# STM_System_Board_Supply.net
KiCad netlist of a schematic drawn in Altium Designer
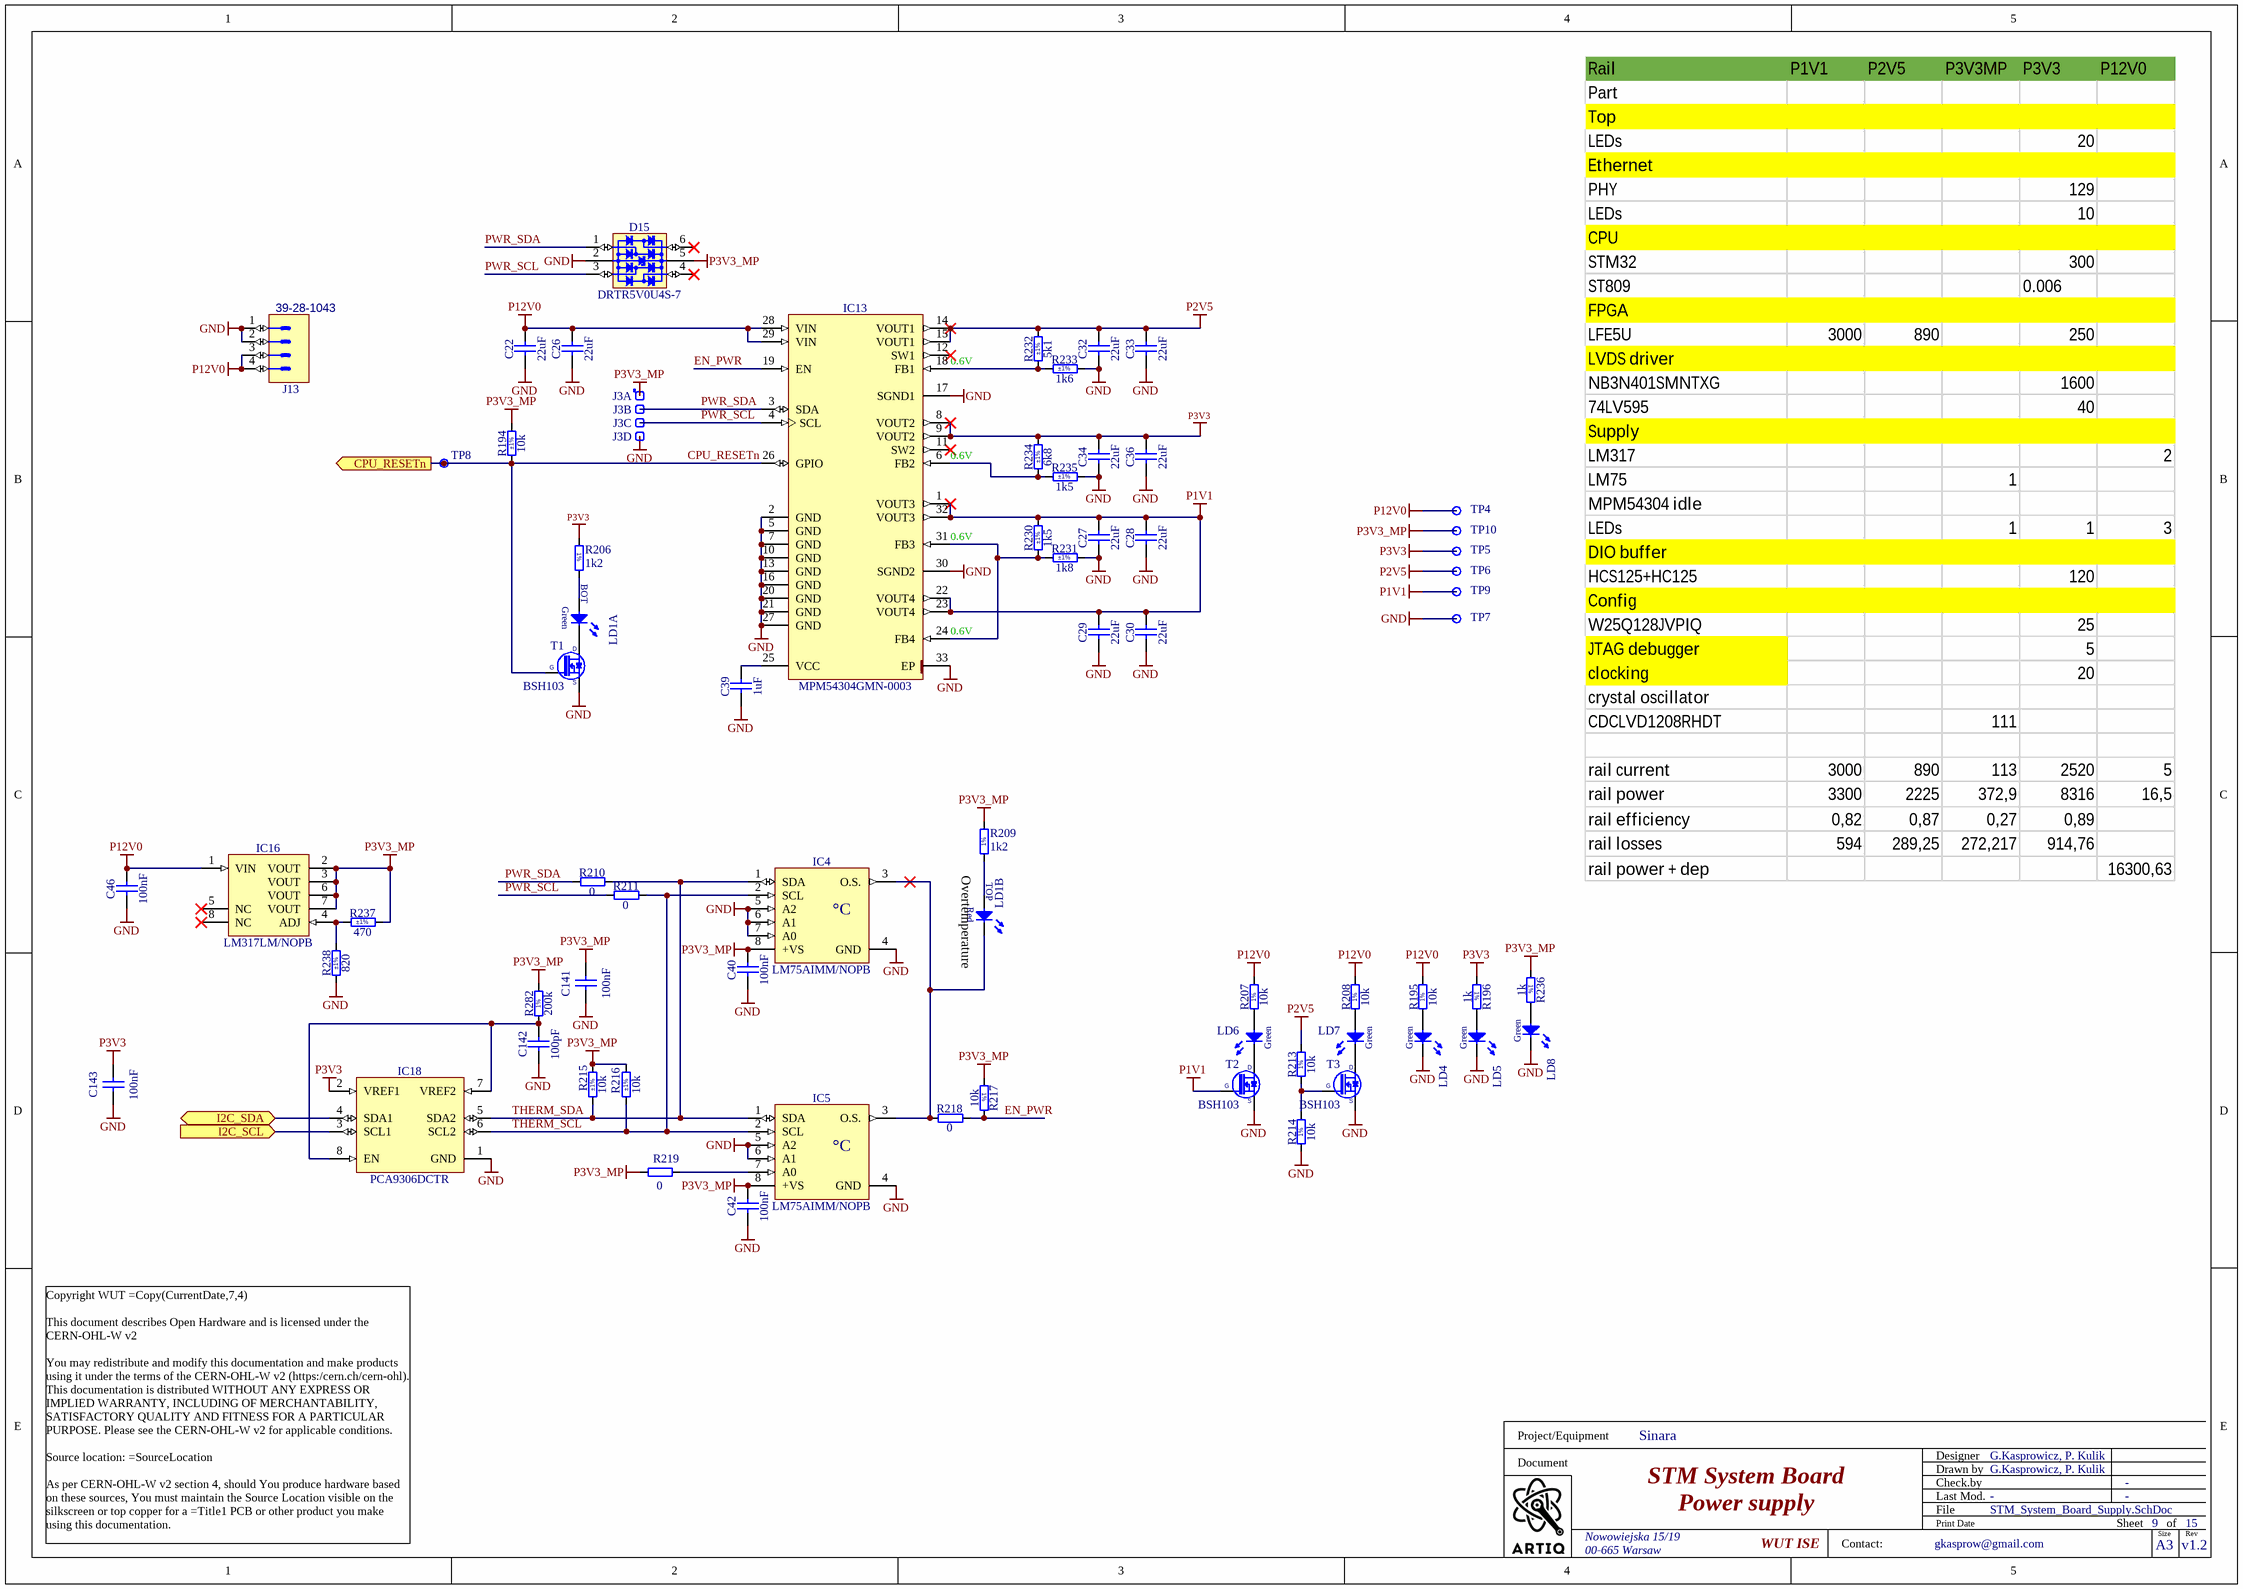
[diagram p0: STM_System_Board_Supply.SchDoc]

(export (version "E")
  (design (tool "Eeschema 10.0.6"))
  (components
    (comp (ref "C22")
      (value "22uF")
      (footprint "CAPC2012X135N")
      (description "Non-polarised capacitor")
      (fields
        (field (name "PART NUMBER") "CC0805_22UF_16V_10%_X5R")
        (field (name "VOLTAGE") "16V")
        (field (name "AUTHOR") "CERN DEM JLC")
      )
      (libsource (lib "Capacitors") (part "Capacitor - non polarized"))
    )
    (comp (ref "C26")
      (value "22uF")
      (footprint "CAPC2012X135N")
      (description "Non-polarised capacitor")
      (fields
        (field (name "PART NUMBER") "CC0805_22UF_16V_10%_X5R")
        (field (name "VOLTAGE") "16V")
        (field (name "AUTHOR") "CERN DEM JLC")
      )
      (libsource (lib "Capacitors") (part "Capacitor - non polarized"))
    )
    (comp (ref "C27")
      (value "22uF")
      (footprint "CAPC2012X135N")
      (description "Non-polarised capacitor")
      (fields
        (field (name "PART NUMBER") "CC0805_22UF_16V_10%_X5R")
        (field (name "VOLTAGE") "16V")
        (field (name "AUTHOR") "CERN DEM JLC")
      )
      (libsource (lib "Capacitors") (part "Capacitor - non polarized"))
    )
    (comp (ref "C28")
      (value "22uF")
      (footprint "CAPC2012X135N")
      (description "Non-polarised capacitor")
      (fields
        (field (name "PART NUMBER") "CC0805_22UF_16V_10%_X5R")
        (field (name "VOLTAGE") "16V")
        (field (name "AUTHOR") "CERN DEM JLC")
      )
      (libsource (lib "Capacitors") (part "Capacitor - non polarized"))
    )
    (comp (ref "C29")
      (value "22uF")
      (footprint "CAPC2012X135N")
      (description "Non-polarised capacitor")
      (fields
        (field (name "PART NUMBER") "CC0805_22UF_16V_10%_X5R")
        (field (name "VOLTAGE") "16V")
        (field (name "AUTHOR") "CERN DEM JLC")
      )
      (libsource (lib "Capacitors") (part "Capacitor - non polarized"))
    )
    (comp (ref "C30")
      (value "22uF")
      (footprint "CAPC2012X135N")
      (description "Non-polarised capacitor")
      (fields
        (field (name "PART NUMBER") "CC0805_22UF_16V_10%_X5R")
        (field (name "VOLTAGE") "16V")
        (field (name "AUTHOR") "CERN DEM JLC")
      )
      (libsource (lib "Capacitors") (part "Capacitor - non polarized"))
    )
    (comp (ref "C32")
      (value "22uF")
      (footprint "CAPC2012X135N")
      (description "Non-polarised capacitor")
      (fields
        (field (name "PART NUMBER") "CC0805_22UF_16V_10%_X5R")
        (field (name "VOLTAGE") "16V")
        (field (name "AUTHOR") "CERN DEM JLC")
      )
      (libsource (lib "Capacitors") (part "Capacitor - non polarized"))
    )
    (comp (ref "C33")
      (value "22uF")
      (footprint "CAPC2012X135N")
      (description "Non-polarised capacitor")
      (fields
        (field (name "PART NUMBER") "CC0805_22UF_16V_10%_X5R")
        (field (name "VOLTAGE") "16V")
        (field (name "AUTHOR") "CERN DEM JLC")
      )
      (libsource (lib "Capacitors") (part "Capacitor - non polarized"))
    )
    (comp (ref "C34")
      (value "22uF")
      (footprint "CAPC2012X135N")
      (description "Non-polarised capacitor")
      (fields
        (field (name "PART NUMBER") "CC0805_22UF_16V_10%_X5R")
        (field (name "VOLTAGE") "16V")
        (field (name "AUTHOR") "CERN DEM JLC")
      )
      (libsource (lib "Capacitors") (part "Capacitor - non polarized"))
    )
    (comp (ref "C36")
      (value "22uF")
      (footprint "CAPC2012X135N")
      (description "Non-polarised capacitor")
      (fields
        (field (name "PART NUMBER") "CC0805_22UF_16V_10%_X5R")
        (field (name "VOLTAGE") "16V")
        (field (name "AUTHOR") "CERN DEM JLC")
      )
      (libsource (lib "Capacitors") (part "Capacitor - non polarized"))
    )
    (comp (ref "C39")
      (value "1uF")
      (footprint "CAPC1005X55N")
      (description "Non-polarised capacitor")
      (fields
        (field (name "PART NUMBER") "CC0402_1UF_16V_10%_X5R")
        (field (name "VOLTAGE") "16V")
        (field (name "AUTHOR") "CERN DEM JLC")
      )
      (libsource (lib "Capacitors") (part "Capacitor - non polarized"))
    )
    (comp (ref "C40")
      (value "100nF")
      (footprint "CAPC1005X55N")
      (description "Non-polarised capacitor")
      (fields
        (field (name "PART NUMBER") "CC0402_100NF_16V_10%_X5R")
        (field (name "VOLTAGE") "16V")
        (field (name "AUTHOR") "CERN DEM JLC")
      )
      (libsource (lib "Capacitors") (part "Capacitor - non polarized"))
    )
    (comp (ref "C42")
      (value "100nF")
      (footprint "CAPC1005X55N")
      (description "Non-polarised capacitor")
      (fields
        (field (name "PART NUMBER") "CC0402_100NF_16V_10%_X5R")
        (field (name "VOLTAGE") "16V")
        (field (name "AUTHOR") "CERN DEM JLC")
      )
      (libsource (lib "Capacitors") (part "Capacitor - non polarized"))
    )
    (comp (ref "C46")
      (value "100nF")
      (footprint "CAPC1005X55N")
      (description "Non-polarised capacitor")
      (fields
        (field (name "PART NUMBER") "CC0402_100NF_16V_10%_X5R")
        (field (name "VOLTAGE") "16V")
        (field (name "AUTHOR") "CERN DEM JLC")
      )
      (libsource (lib "Capacitors") (part "Capacitor - non polarized"))
    )
    (comp (ref "C141")
      (value "100nF")
      (footprint "CAPC1005X55N")
      (description "Non-polarised capacitor")
      (fields
        (field (name "PART NUMBER") "CC0402_100NF_16V_10%_X5R")
        (field (name "VOLTAGE") "16V")
        (field (name "AUTHOR") "CERN DEM JLC")
      )
      (libsource (lib "Capacitors") (part "Capacitor - non polarized"))
    )
    (comp (ref "C142")
      (value "100pF")
      (footprint "CAPC1005X55N")
      (description "Non-polarised capacitor")
      (fields
        (field (name "PART NUMBER") "CC0402_100PF_50V_5%_C0G")
        (field (name "VOLTAGE") "50V")
        (field (name "AUTHOR") "CERN DEM JLC")
      )
      (libsource (lib "Capacitors") (part "Capacitor - non polarized"))
    )
    (comp (ref "C143")
      (value "100nF")
      (footprint "CAPC1005X55N")
      (description "Non-polarised capacitor")
      (fields
        (field (name "PART NUMBER") "CC0402_100NF_16V_10%_X5R")
        (field (name "VOLTAGE") "16V")
        (field (name "AUTHOR") "CERN DEM JLC")
      )
      (libsource (lib "Capacitors") (part "Capacitor - non polarized"))
    )
    (comp (ref "D15")
      (value "DRTR5V0U4S-7")
      (footprint "SOT65P210X110-6N")
      (description "Integrated Quad Ultra-Low Capacitance ESD Protection")
      (fields (field (name "MANUFACTURER") "DIODES") (field (name "AUTHOR") "GK"))
      (libsource (lib "Diodes") (part "D_TVS_DRTR5V0U4S-7"))
    )
    (comp (ref "IC4")
      (value "LM75AIMM/NOPB")
      (footprint "SOP65P490X109-8N")
      (description "Digital Temperature Sensor and Thermal Watchdog with Two-Wire Interface")
      (fields (field (name "MANUFACTURER") "TEXAS INSTRUMENTS") (field (name "AUTHOR") "CERN DEM JLC"))
      (libsource (lib "ICs And Semiconductors") (part "LM75"))
    )
    (comp (ref "IC5")
      (value "LM75AIMM/NOPB")
      (footprint "SOP65P490X109-8N")
      (description "Digital Temperature Sensor and Thermal Watchdog with Two-Wire Interface")
      (fields (field (name "MANUFACTURER") "TEXAS INSTRUMENTS") (field (name "AUTHOR") "CERN DEM JLC"))
      (libsource (lib "ICs And Semiconductors") (part "LM75"))
    )
    (comp (ref "IC13")
      (value "MPM54304GMN-0003")
      (footprint "MPS_MPM54304GMN")
      (description "Quad-Output Power Module with I2C and MTP")
      (fields
        (field (name "MANUFACTURER") "MPS (MONOLITIC  POWER SYSTEMS)")
        (field (name "AUTHOR") "CERN DEM BC")
      )
      (libsource (lib "ICs And Semiconductors") (part "MPM54304GMN"))
    )
    (comp (ref "IC16")
      (value "LM317LM/NOPB")
      (footprint "SOIC127P600X175-8N")
      (description "1.2V to 37V, 100mA Adjustable Positive Regulator")
      (fields (field (name "MANUFACTURER") "TEXAS INSTRUMENTS") (field (name "AUTHOR") "CERN DEM JLC"))
      (libsource (lib "ICs And Semiconductors") (part "LM317LM"))
    )
    (comp (ref "IC18")
      (value "PCA9306DCTR")
      (footprint "SOP65P400X130-8N")
      (description "Dual Bidirectional I2C Bus And SMBus Voltage-Level Translator")
      (fields (field (name "MANUFACTURER") "TEXAS INSTRUMENTS") (field (name "AUTHOR") "CERN DEM JLC"))
      (libsource (lib "ICs And Semiconductors") (part "PCA9306D"))
    )
    (comp (ref "J3")
      (value "Header 4")
      (footprint "SAMTEC_HTSW-104-23-L-S")
      (description "4 Mini Wire-Wrap Contact Strip Header")
      (fields
        (field (name "PART NUMBER") "SAMTEC_HTSW-104-23-L-S")
        (field (name "MANUFACTURER") "SAMTEC")
        (field (name "AUTHOR") "CERN DEM JLC")
      )
      (libsource (lib "Connectors") (part "Wire-Wrap Contact x4"))
    )
    (comp (ref "J13")
      (value "Mini-Fit Jr.™")
      (footprint "MOLEX_39-28-1043")
      (description "Connector 4 Male")
      (fields
        (field (name "MANUFACTURER PART NUMBER") "39-28-1043")
        (field (name "MANUFACTURER") "MOLEX")
        (field (name "PART NUMBER") "MOLEX_39-28-1043")
        (field (name "AUTHOR") "CERN DEM JLC")
      )
      (libsource (lib "Connectors") (part "Connector 4 Male"))
    )
    (comp (ref "LD1")
      (value "Red/Green")
      (footprint "LED_DIALIGHT_571-0112F")
      (description "2x LED  Botom Green, Top Red")
      (fields
        (field (name "PART NUMBER") "LED_DIALIGHT_571-0112F")
        (field (name "MANUFACTURER") "DIALIGHT")
        (field (name "AUTHOR") "CERN DEM JLC")
      )
      (libsource (lib "ICs And Semiconductors") (part "LED x2 G-1C2A-BOT_R-3C4A-TOP"))
    )
    (comp (ref "LD4")
      (value "Green")
      (footprint "LED_KINGBRIGHT_KPH-1608CGCK")
      (description "LED Green 1C 2A")
      (fields
        (field (name "PART NUMBER") "LED_KINGBRIGHT_KPH-1608CGCK")
        (field (name "MANUFACTURER") "KINGBRIGHT")
        (field (name "AUTHOR") "CERN DEM JLC")
      )
      (libsource (lib "ICs And Semiconductors") (part "LED Green 1C 2A"))
    )
    (comp (ref "LD5")
      (value "Green")
      (footprint "LED_KINGBRIGHT_KPH-1608CGCK")
      (description "LED Green 1C 2A")
      (fields
        (field (name "PART NUMBER") "LED_KINGBRIGHT_KPH-1608CGCK")
        (field (name "MANUFACTURER") "KINGBRIGHT")
        (field (name "AUTHOR") "CERN DEM JLC")
      )
      (libsource (lib "ICs And Semiconductors") (part "LED Green 1C 2A"))
    )
    (comp (ref "LD6")
      (value "Green")
      (footprint "LED_KINGBRIGHT_KPH-1608CGCK")
      (description "LED Green 1C 2A")
      (fields
        (field (name "MANUFACTURER PART NUMBER") "KPH-1608CGCK")
        (field (name "PART NUMBER") "LED_KINGBRIGHT_KPH-1608CGCK")
        (field (name "AUTHOR") "CERN DEM JLC")
      )
      (libsource (lib "ICs And Semiconductors") (part "LED Green 1C 2A"))
    )
    (comp (ref "LD7")
      (value "Green")
      (footprint "LED_KINGBRIGHT_KPH-1608CGCK")
      (description "LED Green 1C 2A")
      (fields
        (field (name "MANUFACTURER PART NUMBER") "KPH-1608CGCK")
        (field (name "PART NUMBER") "LED_KINGBRIGHT_KPH-1608CGCK")
        (field (name "AUTHOR") "CERN DEM JLC")
      )
      (libsource (lib "ICs And Semiconductors") (part "LED Green 1C 2A"))
    )
    (comp (ref "LD8")
      (value "Green")
      (footprint "LED_KINGBRIGHT_KPH-1608CGCK")
      (description "LED Green 1C 2A")
      (fields
        (field (name "PART NUMBER") "LED_KINGBRIGHT_KPH-1608CGCK")
        (field (name "MANUFACTURER") "KINGBRIGHT")
        (field (name "AUTHOR") "CERN DEM JLC")
      )
      (libsource (lib "ICs And Semiconductors") (part "LED Green 1C 2A"))
    )
    (comp (ref "R194")
      (value "10k")
      (footprint "RESC1005X40N")
      (description "Resistor - 1%")
      (fields
        (field (name "TOLERANCE") "±1%")
        (field (name "PART NUMBER") "R0402_10K_1%_0.0625W_100PPM")
        (field (name "POWER") "0.0625W")
        (field (name "AUTHOR") "CERN DEM JLC")
      )
      (libsource (lib "Resistors") (part "Resistor - 1%"))
    )
    (comp (ref "R195")
      (value "10k")
      (footprint "RESC1005X40N")
      (description "Resistor - 1%")
      (fields
        (field (name "PART NUMBER") "R0402_10K_1%_0.0625W_100PPM")
        (field (name "POWER") "0.0625W")
        (field (name "AUTHOR") "CERN DEM JLC")
      )
      (libsource (lib "Resistors") (part "Resistor - 1%"))
    )
    (comp (ref "R196")
      (value "1k")
      (footprint "RESC1608X55N")
      (description "Resistor - 1%")
      (fields
        (field (name "PART NUMBER") "R0603_1K_1%_0.1W_100PPM")
        (field (name "POWER") "0.1W")
        (field (name "AUTHOR") "CERN DEM JLC")
      )
      (libsource (lib "Resistors") (part "Resistor - 1%"))
    )
    (comp (ref "R206")
      (value "1k2")
      (footprint "RESC1608X55N")
      (description "Resistor - 1%")
      (fields
        (field (name "PART NUMBER") "R0603_1K2_1%_0.1W_100PPM")
        (field (name "POWER") "0.1W")
        (field (name "AUTHOR") "CERN DEM JLC")
      )
      (libsource (lib "Resistors") (part "Resistor - 1%"))
    )
    (comp (ref "R207")
      (value "10k")
      (footprint "RESC1005X40N")
      (description "Resistor - 1%")
      (fields
        (field (name "PART NUMBER") "R0402_10K_1%_0.0625W_100PPM")
        (field (name "POWER") "0.0625W")
        (field (name "AUTHOR") "CERN DEM JLC")
      )
      (libsource (lib "Resistors") (part "Resistor - 1%"))
    )
    (comp (ref "R208")
      (value "10k")
      (footprint "RESC1005X40N")
      (description "Resistor - 1%")
      (fields
        (field (name "PART NUMBER") "R0402_10K_1%_0.0625W_100PPM")
        (field (name "POWER") "0.0625W")
        (field (name "AUTHOR") "CERN DEM JLC")
      )
      (libsource (lib "Resistors") (part "Resistor - 1%"))
    )
    (comp (ref "R209")
      (value "1k2")
      (footprint "RESC1608X55N")
      (description "Resistor - 1%")
      (fields
        (field (name "PART NUMBER") "R0603_1K2_1%_0.1W_100PPM")
        (field (name "POWER") "0.1W")
        (field (name "AUTHOR") "CERN DEM JLC")
      )
      (libsource (lib "Resistors") (part "Resistor - 1%"))
    )
    (comp (ref "R210")
      (value "0")
      (footprint "RESC1005X40N")
      (description "Resistor")
      (fields
        (field (name "PART NUMBER") "R0402_0R_JUMPER")
        (field (name "MANUFACTURER") "GENERIC")
        (field (name "AUTHOR") "CERN DEM JLC")
      )
      (libsource (lib "Resistors") (part "Resistor"))
    )
    (comp (ref "R211")
      (value "0")
      (footprint "RESC1005X40N")
      (description "Resistor")
      (fields
        (field (name "PART NUMBER") "R0402_0R_JUMPER")
        (field (name "MANUFACTURER") "GENERIC")
        (field (name "AUTHOR") "CERN DEM JLC")
      )
      (libsource (lib "Resistors") (part "Resistor"))
    )
    (comp (ref "R213")
      (value "10k")
      (footprint "RESC1005X40N")
      (description "Resistor - 1%")
      (fields
        (field (name "PART NUMBER") "R0402_10K_1%_0.0625W_100PPM")
        (field (name "POWER") "0.0625W")
        (field (name "AUTHOR") "CERN DEM JLC")
      )
      (libsource (lib "Resistors") (part "Resistor - 1%"))
    )
    (comp (ref "R214")
      (value "10k")
      (footprint "RESC1005X40N")
      (description "Resistor - 1%")
      (fields
        (field (name "PART NUMBER") "R0402_10K_1%_0.0625W_100PPM")
        (field (name "POWER") "0.0625W")
        (field (name "AUTHOR") "CERN DEM JLC")
      )
      (libsource (lib "Resistors") (part "Resistor - 1%"))
    )
    (comp (ref "R215")
      (value "10k")
      (footprint "RESC1005X40N")
      (description "Resistor - 1%")
      (fields
        (field (name "PART NUMBER") "R0402_10K_1%_0.0625W_100PPM")
        (field (name "POWER") "0.0625W")
        (field (name "TOLERANCE") "±1%")
        (field (name "AUTHOR") "CERN DEM JLC")
      )
      (libsource (lib "Resistors") (part "Resistor - 1%"))
    )
    (comp (ref "R216")
      (value "10k")
      (footprint "RESC1005X40N")
      (description "Resistor - 1%")
      (fields
        (field (name "PART NUMBER") "R0402_10K_1%_0.0625W_100PPM")
        (field (name "POWER") "0.0625W")
        (field (name "TOLERANCE") "±1%")
        (field (name "AUTHOR") "CERN DEM JLC")
      )
      (libsource (lib "Resistors") (part "Resistor - 1%"))
    )
    (comp (ref "R217")
      (value "10k")
      (footprint "RESC1005X40N")
      (description "Resistor - 1%")
      (fields
        (field (name "PART NUMBER") "R0402_10K_1%_0.0625W_100PPM")
        (field (name "POWER") "0.0625W")
        (field (name "AUTHOR") "CERN DEM JLC")
      )
      (libsource (lib "Resistors") (part "Resistor - 1%"))
    )
    (comp (ref "R218")
      (value "0")
      (footprint "RESC1005X40N")
      (description "Resistor")
      (fields
        (field (name "PART NUMBER") "R0402_0R_JUMPER")
        (field (name "MANUFACTURER") "GENERIC")
        (field (name "AUTHOR") "CERN DEM JLC")
      )
      (libsource (lib "Resistors") (part "Resistor"))
    )
    (comp (ref "R219")
      (value "0")
      (footprint "RESC1005X40N")
      (description "Resistor")
      (fields
        (field (name "PART NUMBER") "R0402_0R_JUMPER")
        (field (name "MANUFACTURER") "GENERIC")
        (field (name "AUTHOR") "CERN DEM JLC")
      )
      (libsource (lib "Resistors") (part "Resistor"))
    )
    (comp (ref "R230")
      (value "1k5")
      (footprint "RESC1005X40N")
      (description "Resistor - 1%")
      (fields
        (field (name "TOLERANCE") "±1%")
        (field (name "PART NUMBER") "R0402_1K5_1%_0.0625W_100PPM")
        (field (name "POWER") "0.0625W")
        (field (name "AUTHOR") "CERN DEM JLC")
      )
      (libsource (lib "Resistors") (part "Resistor - 1%"))
    )
    (comp (ref "R231")
      (value "1k8")
      (footprint "RESC1005X40N")
      (description "Resistor - 1%")
      (fields
        (field (name "TOLERANCE") "±1%")
        (field (name "PART NUMBER") "R0402_1K8_1%_0.0625W_100PPM")
        (field (name "POWER") "0.0625W")
        (field (name "AUTHOR") "CERN DEM JLC")
      )
      (libsource (lib "Resistors") (part "Resistor - 1%"))
    )
    (comp (ref "R232")
      (value "5k1")
      (footprint "RESC1005X40N")
      (description "Resistor - 1%")
      (fields
        (field (name "TOLERANCE") "±1%")
        (field (name "PART NUMBER") "R0402_5K1_1%_0.0625W_100PPM")
        (field (name "POWER") "0.0625W")
        (field (name "AUTHOR") "CERN DEM JLC")
      )
      (libsource (lib "Resistors") (part "Resistor - 1%"))
    )
    (comp (ref "R233")
      (value "1k6")
      (footprint "RESC1005X40N")
      (description "Resistor - 1%")
      (fields
        (field (name "TOLERANCE") "±1%")
        (field (name "PART NUMBER") "R0402_1K6_1%_0.0625W_100PPM")
        (field (name "POWER") "0.0625W")
        (field (name "AUTHOR") "CERN DEM JLC")
      )
      (libsource (lib "Resistors") (part "Resistor - 1%"))
    )
    (comp (ref "R234")
      (value "6k8")
      (footprint "RESC1005X40N")
      (description "Resistor - 1%")
      (fields
        (field (name "TOLERANCE") "±1%")
        (field (name "PART NUMBER") "R0402_6K8_1%_0.0625W_100PPM")
        (field (name "POWER") "0.0625W")
        (field (name "AUTHOR") "CERN DEM JLC")
      )
      (libsource (lib "Resistors") (part "Resistor - 1%"))
    )
    (comp (ref "R235")
      (value "1k5")
      (footprint "RESC1005X40N")
      (description "Resistor - 1%")
      (fields
        (field (name "TOLERANCE") "±1%")
        (field (name "PART NUMBER") "R0402_1K5_1%_0.0625W_100PPM")
        (field (name "POWER") "0.0625W")
        (field (name "AUTHOR") "CERN DEM JLC")
      )
      (libsource (lib "Resistors") (part "Resistor - 1%"))
    )
    (comp (ref "R236")
      (value "1k")
      (footprint "RESC1608X55N")
      (description "Resistor - 1%")
      (fields
        (field (name "PART NUMBER") "R0603_1K_1%_0.1W_100PPM")
        (field (name "POWER") "0.1W")
        (field (name "AUTHOR") "CERN DEM JLC")
      )
      (libsource (lib "Resistors") (part "Resistor - 1%"))
    )
    (comp (ref "R237")
      (value "470")
      (footprint "RESC1005X40N")
      (description "Resistor - 1%")
      (fields
        (field (name "TOLERANCE") "±1%")
        (field (name "PART NUMBER") "R0402_470R_1%_0.0625W_100PPM")
        (field (name "POWER") "0.0625W")
        (field (name "AUTHOR") "CERN DEM JLC")
      )
      (libsource (lib "Resistors") (part "Resistor - 1%"))
    )
    (comp (ref "R238")
      (value "820")
      (footprint "RESC1005X40N")
      (description "Resistor - 1%")
      (fields
        (field (name "TOLERANCE") "±1%")
        (field (name "PART NUMBER") "R0402_820R_1%_0.0625W_100PPM")
        (field (name "POWER") "0.0625W")
        (field (name "AUTHOR") "CERN DEM JLC")
      )
      (libsource (lib "Resistors") (part "Resistor - 1%"))
    )
    (comp (ref "R282")
      (value "200k")
      (footprint "RESC1005X40N")
      (description "Resistor - 1%")
      (fields
        (field (name "PART NUMBER") "R0402_200K_1%_0.0625W_100PPM")
        (field (name "POWER") "0.0625W")
        (field (name "AUTHOR") "CERN DEM JLC")
      )
      (libsource (lib "Resistors") (part "Resistor - 1%"))
    )
    (comp (ref "T1")
      (value "BSH103")
      (footprint "SOT95P230X110-3N")
      (description "N-CHANNEL MOSFET WITH DIODE")
      (fields (field (name "MANUFACTURER") "NEXPERIA") (field (name "AUTHOR") "CERN DEM JLC"))
      (libsource (lib "ICs And Semiconductors") (part "N-MOSFET-D 1G 2S 3D"))
    )
    (comp (ref "T2")
      (value "BSH103")
      (footprint "SOT95P230X110-3N")
      (description "N-CHANNEL MOSFET WITH DIODE")
      (fields (field (name "MANUFACTURER") "NEXPERIA") (field (name "AUTHOR") "CERN DEM JLC"))
      (libsource (lib "ICs And Semiconductors") (part "N-MOSFET-D 1G 2S 3D"))
    )
    (comp (ref "T3")
      (value "BSH103")
      (footprint "SOT95P230X110-3N")
      (description "N-CHANNEL MOSFET WITH DIODE")
      (fields (field (name "MANUFACTURER") "NEXPERIA") (field (name "AUTHOR") "CERN DEM JLC"))
      (libsource (lib "ICs And Semiconductors") (part "N-MOSFET-D 1G 2S 3D"))
    )
    (comp (ref "TP4")
      (value "Test Point")
      (footprint "TPS127")
      (fields (field (name "PART NUMBER") "SMD_PAD_1.27X1.27MM") (field (name "AUTHOR") "CERN DEM JLC"))
      (libsource (lib "Eletro-mechanical") (part "Test Point"))
    )
    (comp (ref "TP5")
      (value "Test Point")
      (footprint "TPS127")
      (fields (field (name "PART NUMBER") "SMD_PAD_1.27X1.27MM") (field (name "AUTHOR") "CERN DEM JLC"))
      (libsource (lib "Eletro-mechanical") (part "Test Point"))
    )
    (comp (ref "TP6")
      (value "Test Point")
      (footprint "TPS127")
      (fields (field (name "PART NUMBER") "SMD_PAD_1.27X1.27MM") (field (name "AUTHOR") "CERN DEM JLC"))
      (libsource (lib "Eletro-mechanical") (part "Test Point"))
    )
    (comp (ref "TP7")
      (value "Test Point")
      (footprint "TPS127")
      (fields (field (name "PART NUMBER") "SMD_PAD_1.27X1.27MM") (field (name "AUTHOR") "CERN DEM JLC"))
      (libsource (lib "Eletro-mechanical") (part "Test Point"))
    )
    (comp (ref "TP8")
      (value "Test Point")
      (footprint "TPS127")
      (fields (field (name "PART NUMBER") "SMD_PAD_1.27X1.27MM") (field (name "AUTHOR") "CERN DEM JLC"))
      (libsource (lib "Eletro-mechanical") (part "Test Point"))
    )
    (comp (ref "TP9")
      (value "Test Point")
      (footprint "TPS127")
      (fields (field (name "PART NUMBER") "SMD_PAD_1.27X1.27MM") (field (name "AUTHOR") "CERN DEM JLC"))
      (libsource (lib "Eletro-mechanical") (part "Test Point"))
    )
    (comp (ref "TP10")
      (value "Test Point")
      (footprint "TPS127")
      (fields (field (name "PART NUMBER") "SMD_PAD_1.27X1.27MM") (field (name "AUTHOR") "CERN DEM JLC"))
      (libsource (lib "Eletro-mechanical") (part "Test Point"))
    )
  )
  (nets
    (net (code "1") (name "/CPU_RESETn") (class "Default")
      (node (ref "IC13") (pin "26") (pinfunction "GPIO_26") (pintype "bidirectional"))
      (node (ref "R194") (pin "1") (pinfunction "1_1") (pintype "passive"))
      (node (ref "T1") (pin "1") (pinfunction "G_1") (pintype "passive"))
      (node (ref "TP8") (pin "1") (pinfunction "1_1") (pintype "bidirectional"))
    )
    (net (code "2") (name "/EN_PWR") (class "Default")
      (node (ref "IC13") (pin "19") (pinfunction "EN_19") (pintype "input"))
      (node (ref "R217") (pin "2") (pinfunction "2_2") (pintype "passive"))
      (node (ref "R218") (pin "2") (pinfunction "2_2") (pintype "passive"))
    )
    (net (code "3") (name "/I2C_SCL") (class "Default")
      (node (ref "IC18") (pin "3") (pinfunction "SCL1_3") (pintype "bidirectional"))
    )
    (net (code "4") (name "/I2C_SDA") (class "Default")
      (node (ref "IC18") (pin "4") (pinfunction "SDA1_4") (pintype "bidirectional"))
    )
    (net (code "5") (name "/PWR_SCL") (class "Default")
      (node (ref "D15") (pin "3") (pinfunction "I/O2_3") (pintype "bidirectional"))
      (node (ref "IC13") (pin "4") (pinfunction "SCL_4") (pintype "input"))
      (node (ref "J3") (pin "3") (pinfunction "3_3") (pintype "bidirectional"))
      (node (ref "R211") (pin "1") (pinfunction "1_1") (pintype "passive"))
    )
    (net (code "6") (name "/PWR_SDA") (class "Default")
      (node (ref "D15") (pin "1") (pinfunction "I/O1_1") (pintype "bidirectional"))
      (node (ref "IC13") (pin "3") (pinfunction "SDA_3") (pintype "bidirectional"))
      (node (ref "J3") (pin "2") (pinfunction "2_2") (pintype "bidirectional"))
      (node (ref "R210") (pin "1") (pinfunction "1_1") (pintype "passive"))
    )
    (net (code "7") (name "/THERM_SCL") (class "Default")
      (node (ref "IC18") (pin "6") (pinfunction "SCL2_6") (pintype "bidirectional"))
      (node (ref "IC4") (pin "2") (pinfunction "SCL_2") (pintype "input"))
      (node (ref "IC5") (pin "2") (pinfunction "SCL_2") (pintype "input"))
      (node (ref "R211") (pin "2") (pinfunction "2_2") (pintype "passive"))
      (node (ref "R216") (pin "1") (pinfunction "1_1") (pintype "passive"))
    )
    (net (code "8") (name "/THERM_SDA") (class "Default")
      (node (ref "IC18") (pin "5") (pinfunction "SDA2_5") (pintype "bidirectional"))
      (node (ref "IC4") (pin "1") (pinfunction "SDA_1") (pintype "bidirectional"))
      (node (ref "IC5") (pin "1") (pinfunction "SDA_1") (pintype "bidirectional"))
      (node (ref "R210") (pin "2") (pinfunction "2_2") (pintype "passive"))
      (node (ref "R215") (pin "1") (pinfunction "1_1") (pintype "passive"))
    )
    (net (code "9") (name "GND") (class "Default")
      (node (ref "C141") (pin "1") (pinfunction "1_1") (pintype "passive"))
      (node (ref "C142") (pin "1") (pinfunction "1_1") (pintype "passive"))
      (node (ref "C143") (pin "1") (pinfunction "1_1") (pintype "passive"))
      (node (ref "C22") (pin "1") (pinfunction "1_1") (pintype "passive"))
      (node (ref "C26") (pin "1") (pinfunction "1_1") (pintype "passive"))
      (node (ref "C27") (pin "1") (pinfunction "1_1") (pintype "passive"))
      (node (ref "C28") (pin "1") (pinfunction "1_1") (pintype "passive"))
      (node (ref "C29") (pin "1") (pinfunction "1_1") (pintype "passive"))
      (node (ref "C30") (pin "1") (pinfunction "1_1") (pintype "passive"))
      (node (ref "C32") (pin "1") (pinfunction "1_1") (pintype "passive"))
      (node (ref "C33") (pin "1") (pinfunction "1_1") (pintype "passive"))
      (node (ref "C34") (pin "1") (pinfunction "1_1") (pintype "passive"))
      (node (ref "C36") (pin "1") (pinfunction "1_1") (pintype "passive"))
      (node (ref "C39") (pin "1") (pinfunction "1_1") (pintype "passive"))
      (node (ref "C40") (pin "1") (pinfunction "1_1") (pintype "passive"))
      (node (ref "C42") (pin "1") (pinfunction "1_1") (pintype "passive"))
      (node (ref "C46") (pin "1") (pinfunction "1_1") (pintype "passive"))
      (node (ref "D15") (pin "2") (pinfunction "GND_2") (pintype "power_in"))
      (node (ref "IC13") (pin "10") (pinfunction "GND_10") (pintype "power_in"))
      (node (ref "IC13") (pin "13") (pinfunction "GND_13") (pintype "power_in"))
      (node (ref "IC13") (pin "16") (pinfunction "GND_16") (pintype "power_in"))
      (node (ref "IC13") (pin "17") (pinfunction "SGND1_17") (pintype "power_in"))
      (node (ref "IC13") (pin "2") (pinfunction "GND_2") (pintype "power_in"))
      (node (ref "IC13") (pin "20") (pinfunction "GND_20") (pintype "power_in"))
      (node (ref "IC13") (pin "21") (pinfunction "GND_21") (pintype "power_in"))
      (node (ref "IC13") (pin "27") (pinfunction "GND_27") (pintype "power_in"))
      (node (ref "IC13") (pin "30") (pinfunction "SGND2_30") (pintype "power_in"))
      (node (ref "IC13") (pin "33") (pinfunction "EP_33") (pintype "power_in"))
      (node (ref "IC13") (pin "5") (pinfunction "GND_5") (pintype "power_in"))
      (node (ref "IC13") (pin "7") (pinfunction "GND_7") (pintype "power_in"))
      (node (ref "IC18") (pin "1") (pinfunction "GND_1") (pintype "power_in"))
      (node (ref "IC4") (pin "4") (pinfunction "GND_4") (pintype "power_in"))
      (node (ref "IC4") (pin "5") (pinfunction "A2_5") (pintype "input"))
      (node (ref "IC4") (pin "6") (pinfunction "A1_6") (pintype "input"))
      (node (ref "IC4") (pin "7") (pinfunction "A0_7") (pintype "input"))
      (node (ref "IC5") (pin "4") (pinfunction "GND_4") (pintype "power_in"))
      (node (ref "IC5") (pin "5") (pinfunction "A2_5") (pintype "input"))
      (node (ref "IC5") (pin "6") (pinfunction "A1_6") (pintype "input"))
      (node (ref "J13") (pin "1") (pinfunction "1_1") (pintype "bidirectional"))
      (node (ref "J13") (pin "2") (pinfunction "2_2") (pintype "bidirectional"))
      (node (ref "J3") (pin "4") (pinfunction "4_4") (pintype "bidirectional"))
      (node (ref "LD4") (pin "1") (pinfunction "C_1") (pintype "passive"))
      (node (ref "LD5") (pin "1") (pinfunction "C_1") (pintype "passive"))
      (node (ref "LD8") (pin "1") (pinfunction "C_1") (pintype "passive"))
      (node (ref "R214") (pin "1") (pinfunction "1_1") (pintype "passive"))
      (node (ref "R231") (pin "2") (pinfunction "2_2") (pintype "passive"))
      (node (ref "R233") (pin "2") (pinfunction "2_2") (pintype "passive"))
      (node (ref "R235") (pin "2") (pinfunction "2_2") (pintype "passive"))
      (node (ref "R238") (pin "1") (pinfunction "1_1") (pintype "passive"))
      (node (ref "T1") (pin "2") (pinfunction "S_2") (pintype "passive"))
      (node (ref "T2") (pin "2") (pinfunction "S_2") (pintype "passive"))
      (node (ref "T3") (pin "2") (pinfunction "S_2") (pintype "passive"))
      (node (ref "TP7") (pin "1") (pinfunction "1_1") (pintype "bidirectional"))
    )
    (net (code "10") (name "Net-(IC4-O.S.)") (class "Default")
      (node (ref "IC4") (pin "3") (pinfunction "O.S._3") (pintype "output"))
      (node (ref "IC5") (pin "3") (pinfunction "O.S._3") (pintype "output"))
      (node (ref "LD1") (pin "3") (pinfunction "C_3") (pintype "passive"))
      (node (ref "R218") (pin "1") (pinfunction "1_1") (pintype "passive"))
    )
    (net (code "11") (name "Net-(IC5-A0)") (class "Default")
      (node (ref "IC5") (pin "7") (pinfunction "A0_7") (pintype "input"))
      (node (ref "R219") (pin "2") (pinfunction "2_2") (pintype "passive"))
    )
    (net (code "12") (name "Net-(IC13-FB1)") (class "Default")
      (node (ref "IC13") (pin "18") (pinfunction "FB1_18") (pintype "input"))
      (node (ref "R232") (pin "1") (pinfunction "1_1") (pintype "passive"))
      (node (ref "R233") (pin "1") (pinfunction "1_1") (pintype "passive"))
    )
    (net (code "13") (name "Net-(IC13-FB2)") (class "Default")
      (node (ref "IC13") (pin "6") (pinfunction "FB2_6") (pintype "input"))
      (node (ref "R234") (pin "1") (pinfunction "1_1") (pintype "passive"))
      (node (ref "R235") (pin "1") (pinfunction "1_1") (pintype "passive"))
    )
    (net (code "14") (name "Net-(IC13-FB3)") (class "Default")
      (node (ref "IC13") (pin "24") (pinfunction "FB4_24") (pintype "input"))
      (node (ref "IC13") (pin "31") (pinfunction "FB3_31") (pintype "input"))
      (node (ref "R230") (pin "1") (pinfunction "1_1") (pintype "passive"))
      (node (ref "R231") (pin "1") (pinfunction "1_1") (pintype "passive"))
    )
    (net (code "15") (name "Net-(IC13-VCC)") (class "Default")
      (node (ref "C39") (pin "2") (pinfunction "2_2") (pintype "passive"))
      (node (ref "IC13") (pin "25") (pinfunction "VCC_25") (pintype "power_in"))
    )
    (net (code "16") (name "Net-(IC16-ADJ)") (class "Default")
      (node (ref "IC16") (pin "4") (pinfunction "ADJ_4") (pintype "input"))
      (node (ref "R237") (pin "1") (pinfunction "1_1") (pintype "passive"))
      (node (ref "R238") (pin "2") (pinfunction "2_2") (pintype "passive"))
    )
    (net (code "17") (name "Net-(IC18-EN)") (class "Default")
      (node (ref "C142") (pin "2") (pinfunction "2_2") (pintype "passive"))
      (node (ref "IC18") (pin "7") (pinfunction "VREF2_7") (pintype "input"))
      (node (ref "IC18") (pin "8") (pinfunction "EN_8") (pintype "input"))
      (node (ref "R282") (pin "1") (pinfunction "1_1") (pintype "passive"))
    )
    (net (code "18") (name "Net-(LD1A-A)") (class "Default")
      (node (ref "LD1") (pin "2") (pinfunction "A_2") (pintype "passive"))
      (node (ref "R206") (pin "2") (pinfunction "2_2") (pintype "passive"))
    )
    (net (code "19") (name "Net-(LD1A-C)") (class "Default")
      (node (ref "LD1") (pin "1") (pinfunction "C_1") (pintype "passive"))
      (node (ref "T1") (pin "3") (pinfunction "D_3") (pintype "passive"))
    )
    (net (code "20") (name "Net-(LD1B-A)") (class "Default")
      (node (ref "LD1") (pin "4") (pinfunction "A_4") (pintype "passive"))
      (node (ref "R209") (pin "1") (pinfunction "1_1") (pintype "passive"))
    )
    (net (code "21") (name "Net-(LD4-A)") (class "Default")
      (node (ref "LD4") (pin "2") (pinfunction "A_2") (pintype "passive"))
      (node (ref "R195") (pin "1") (pinfunction "1_1") (pintype "passive"))
    )
    (net (code "22") (name "Net-(LD5-A)") (class "Default")
      (node (ref "LD5") (pin "2") (pinfunction "A_2") (pintype "passive"))
      (node (ref "R196") (pin "2") (pinfunction "2_2") (pintype "passive"))
    )
    (net (code "23") (name "Net-(LD6-A)") (class "Default")
      (node (ref "LD6") (pin "2") (pinfunction "A_2") (pintype "passive"))
      (node (ref "R207") (pin "1") (pinfunction "1_1") (pintype "passive"))
    )
    (net (code "24") (name "Net-(LD6-C)") (class "Default")
      (node (ref "LD6") (pin "1") (pinfunction "C_1") (pintype "passive"))
      (node (ref "T2") (pin "3") (pinfunction "D_3") (pintype "passive"))
    )
    (net (code "25") (name "Net-(LD7-A)") (class "Default")
      (node (ref "LD7") (pin "2") (pinfunction "A_2") (pintype "passive"))
      (node (ref "R208") (pin "1") (pinfunction "1_1") (pintype "passive"))
    )
    (net (code "26") (name "Net-(LD7-C)") (class "Default")
      (node (ref "LD7") (pin "1") (pinfunction "C_1") (pintype "passive"))
      (node (ref "T3") (pin "3") (pinfunction "D_3") (pintype "passive"))
    )
    (net (code "27") (name "Net-(LD8-A)") (class "Default")
      (node (ref "LD8") (pin "2") (pinfunction "A_2") (pintype "passive"))
      (node (ref "R236") (pin "2") (pinfunction "2_2") (pintype "passive"))
    )
    (net (code "28") (name "Net-(T3-G)") (class "Default")
      (node (ref "R213") (pin "1") (pinfunction "1_1") (pintype "passive"))
      (node (ref "R214") (pin "2") (pinfunction "2_2") (pintype "passive"))
      (node (ref "T3") (pin "1") (pinfunction "G_1") (pintype "passive"))
    )
    (net (code "29") (name "P1V1") (class "Default")
      (node (ref "C27") (pin "2") (pinfunction "2_2") (pintype "passive"))
      (node (ref "C28") (pin "2") (pinfunction "2_2") (pintype "passive"))
      (node (ref "C29") (pin "2") (pinfunction "2_2") (pintype "passive"))
      (node (ref "C30") (pin "2") (pinfunction "2_2") (pintype "passive"))
      (node (ref "IC13") (pin "1") (pinfunction "VOUT3_1") (pintype "output"))
      (node (ref "IC13") (pin "22") (pinfunction "VOUT4_22") (pintype "output"))
      (node (ref "IC13") (pin "23") (pinfunction "VOUT4_23") (pintype "output"))
      (node (ref "IC13") (pin "32") (pinfunction "VOUT3_32") (pintype "output"))
      (node (ref "R230") (pin "2") (pinfunction "2_2") (pintype "passive"))
      (node (ref "T2") (pin "1") (pinfunction "G_1") (pintype "passive"))
      (node (ref "TP9") (pin "1") (pinfunction "1_1") (pintype "bidirectional"))
    )
    (net (code "30") (name "P2V5") (class "Default")
      (node (ref "C32") (pin "2") (pinfunction "2_2") (pintype "passive"))
      (node (ref "C33") (pin "2") (pinfunction "2_2") (pintype "passive"))
      (node (ref "IC13") (pin "14") (pinfunction "VOUT1_14") (pintype "output"))
      (node (ref "IC13") (pin "15") (pinfunction "VOUT1_15") (pintype "output"))
      (node (ref "R213") (pin "2") (pinfunction "2_2") (pintype "passive"))
      (node (ref "R232") (pin "2") (pinfunction "2_2") (pintype "passive"))
      (node (ref "TP6") (pin "1") (pinfunction "1_1") (pintype "bidirectional"))
    )
    (net (code "31") (name "P3V3") (class "Default")
      (node (ref "C143") (pin "2") (pinfunction "2_2") (pintype "passive"))
      (node (ref "C34") (pin "2") (pinfunction "2_2") (pintype "passive"))
      (node (ref "C36") (pin "2") (pinfunction "2_2") (pintype "passive"))
      (node (ref "IC13") (pin "8") (pinfunction "VOUT2_8") (pintype "output"))
      (node (ref "IC13") (pin "9") (pinfunction "VOUT2_9") (pintype "output"))
      (node (ref "IC18") (pin "2") (pinfunction "VREF1_2") (pintype "input"))
      (node (ref "R196") (pin "1") (pinfunction "1_1") (pintype "passive"))
      (node (ref "R206") (pin "1") (pinfunction "1_1") (pintype "passive"))
      (node (ref "R234") (pin "2") (pinfunction "2_2") (pintype "passive"))
      (node (ref "TP5") (pin "1") (pinfunction "1_1") (pintype "bidirectional"))
    )
    (net (code "32") (name "P3V3_MP") (class "Default")
      (node (ref "C141") (pin "2") (pinfunction "2_2") (pintype "passive"))
      (node (ref "C40") (pin "2") (pinfunction "2_2") (pintype "passive"))
      (node (ref "C42") (pin "2") (pinfunction "2_2") (pintype "passive"))
      (node (ref "D15") (pin "5") (pinfunction "VBUS_5") (pintype "power_in"))
      (node (ref "IC16") (pin "2") (pinfunction "VOUT_2") (pintype "power_in"))
      (node (ref "IC16") (pin "3") (pinfunction "VOUT_3") (pintype "power_in"))
      (node (ref "IC16") (pin "6") (pinfunction "VOUT_6") (pintype "power_in"))
      (node (ref "IC16") (pin "7") (pinfunction "VOUT_7") (pintype "power_in"))
      (node (ref "IC4") (pin "8") (pinfunction "+VS_8") (pintype "power_in"))
      (node (ref "IC5") (pin "8") (pinfunction "+VS_8") (pintype "power_in"))
      (node (ref "J3") (pin "1") (pinfunction "1_1") (pintype "bidirectional"))
      (node (ref "R194") (pin "2") (pinfunction "2_2") (pintype "passive"))
      (node (ref "R209") (pin "2") (pinfunction "2_2") (pintype "passive"))
      (node (ref "R215") (pin "2") (pinfunction "2_2") (pintype "passive"))
      (node (ref "R216") (pin "2") (pinfunction "2_2") (pintype "passive"))
      (node (ref "R217") (pin "1") (pinfunction "1_1") (pintype "passive"))
      (node (ref "R219") (pin "1") (pinfunction "1_1") (pintype "passive"))
      (node (ref "R236") (pin "1") (pinfunction "1_1") (pintype "passive"))
      (node (ref "R237") (pin "2") (pinfunction "2_2") (pintype "passive"))
      (node (ref "R282") (pin "2") (pinfunction "2_2") (pintype "passive"))
      (node (ref "TP10") (pin "1") (pinfunction "1_1") (pintype "bidirectional"))
    )
    (net (code "33") (name "P12V0") (class "Default")
      (node (ref "C22") (pin "2") (pinfunction "2_2") (pintype "passive"))
      (node (ref "C26") (pin "2") (pinfunction "2_2") (pintype "passive"))
      (node (ref "C46") (pin "2") (pinfunction "2_2") (pintype "passive"))
      (node (ref "IC13") (pin "28") (pinfunction "VIN_28") (pintype "input"))
      (node (ref "IC13") (pin "29") (pinfunction "VIN_29") (pintype "input"))
      (node (ref "IC16") (pin "1") (pinfunction "VIN_1") (pintype "input"))
      (node (ref "J13") (pin "3") (pinfunction "3_3") (pintype "bidirectional"))
      (node (ref "J13") (pin "4") (pinfunction "4_4") (pintype "bidirectional"))
      (node (ref "R195") (pin "2") (pinfunction "2_2") (pintype "passive"))
      (node (ref "R207") (pin "2") (pinfunction "2_2") (pintype "passive"))
      (node (ref "R208") (pin "2") (pinfunction "2_2") (pintype "passive"))
      (node (ref "TP4") (pin "1") (pinfunction "1_1") (pintype "bidirectional"))
    )
    (net (code "34") (name "unconnected-(D15-I{slash}O3-Pad4)") (class "Default")
      (node (ref "D15") (pin "4") (pinfunction "I/O3_4") (pintype "bidirectional+no_connect"))
    )
    (net (code "35") (name "unconnected-(D15-I{slash}O4-Pad6)") (class "Default")
      (node (ref "D15") (pin "6") (pinfunction "I/O4_6") (pintype "bidirectional+no_connect"))
    )
    (net (code "36") (name "unconnected-(IC13-SW1-Pad12)") (class "Default")
      (node (ref "IC13") (pin "12") (pinfunction "SW1_12") (pintype "output+no_connect"))
    )
    (net (code "37") (name "unconnected-(IC13-SW2-Pad11)") (class "Default")
      (node (ref "IC13") (pin "11") (pinfunction "SW2_11") (pintype "output+no_connect"))
    )
    (net (code "38") (name "unconnected-(IC16-NC-Pad5)") (class "Default")
      (node (ref "IC16") (pin "5") (pinfunction "NC_5") (pintype "passive+no_connect"))
    )
    (net (code "39") (name "unconnected-(IC16-NC-Pad8)") (class "Default")
      (node (ref "IC16") (pin "8") (pinfunction "NC_8") (pintype "passive+no_connect"))
    )
  )
)
